# PIC.net
KiCad netlist of a schematic drawn in Altium Designer
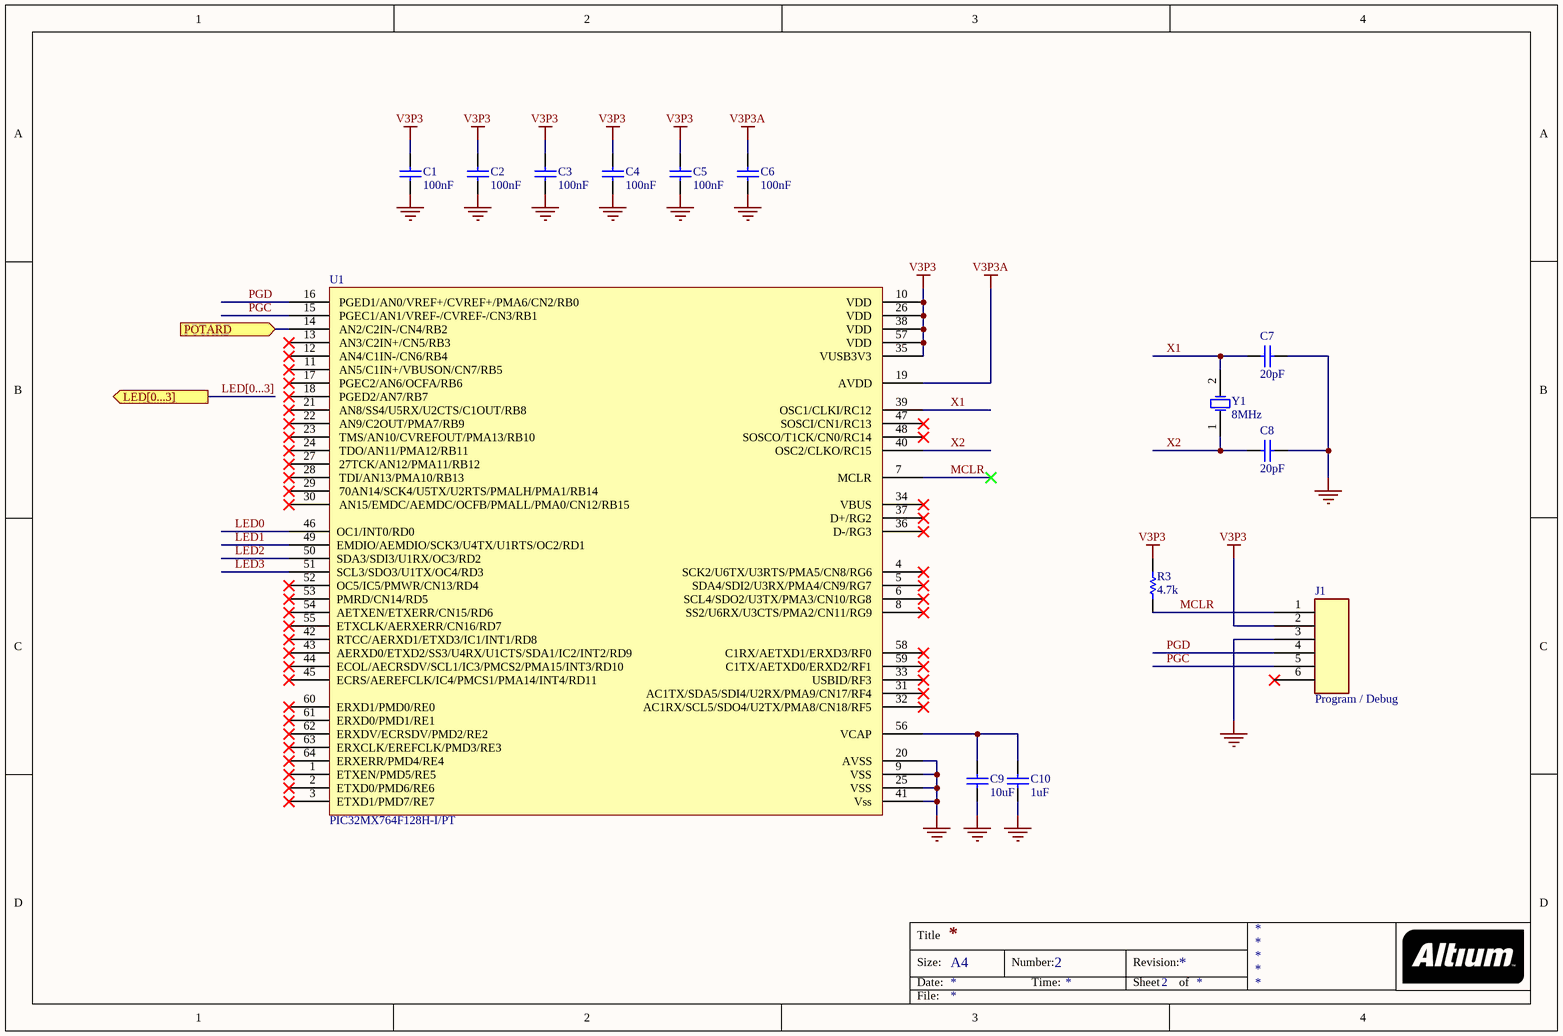
[diagram p0: PIC.SchDoc]

(export (version "E")
  (design (tool "Eeschema 10.0.6"))
  (components
    (comp (ref "C1")
      (value "100nF")
      (footprint "CAPC1608N")
      (description "Capacitor")
      (fields (field (name "PUBLISHER") "Altium Limited"))
      (libsource (lib "Miscellaneous Devices") (part "Cap"))
    )
    (comp (ref "C2")
      (value "100nF")
      (footprint "CAPC1608N")
      (description "Capacitor")
      (fields (field (name "PUBLISHER") "Altium Limited"))
      (libsource (lib "Miscellaneous Devices") (part "Cap"))
    )
    (comp (ref "C3")
      (value "100nF")
      (footprint "CAPC1608N")
      (description "Capacitor")
      (fields (field (name "PUBLISHER") "Altium Limited"))
      (libsource (lib "Miscellaneous Devices") (part "Cap"))
    )
    (comp (ref "C4")
      (value "100nF")
      (footprint "CAPC1608N")
      (description "Capacitor")
      (fields (field (name "PUBLISHER") "Altium Limited"))
      (libsource (lib "Miscellaneous Devices") (part "Cap"))
    )
    (comp (ref "C5")
      (value "100nF")
      (footprint "CAPC1608N")
      (description "Capacitor")
      (fields (field (name "PUBLISHER") "Altium Limited"))
      (libsource (lib "Miscellaneous Devices") (part "Cap"))
    )
    (comp (ref "C6")
      (value "100nF")
      (footprint "CAPC1608N")
      (description "Capacitor")
      (fields (field (name "PUBLISHER") "Altium Limited"))
      (libsource (lib "Miscellaneous Devices") (part "Cap"))
    )
    (comp (ref "C7")
      (value "20pF")
      (footprint "CAPC1005N")
      (description "Capacitor")
      (fields (field (name "PUBLISHER") "Altium Limited"))
      (libsource (lib "Miscellaneous Devices") (part "Cap"))
    )
    (comp (ref "C8")
      (value "20pF")
      (footprint "CAPC1005N")
      (description "Capacitor")
      (fields (field (name "PUBLISHER") "Altium Limited"))
      (libsource (lib "Miscellaneous Devices") (part "Cap"))
    )
    (comp (ref "C9")
      (value "10uF")
      (footprint "CAPC2012N")
      (description "Capacitor")
      (fields (field (name "PUBLISHER") "Altium Limited"))
      (libsource (lib "Miscellaneous Devices") (part "Cap"))
    )
    (comp (ref "C10")
      (value "1uF")
      (footprint "CAPC1608N")
      (description "Capacitor")
      (fields (field (name "PUBLISHER") "Altium Limited"))
      (libsource (lib "Miscellaneous Devices") (part "Cap"))
    )
    (comp (ref "J1")
      (value "Program / Debug")
      (fields (field (name "NAME") "J1") (field (name "TYPE") "Program / Debug"))
      (libsource (lib "TP02_SCHLib") (part "Program / Debug"))
    )
    (comp (ref "R3")
      (value "4.7k")
      (footprint "RESC1608N")
      (description "Resistor")
      (fields (field (name "PUBLISHER") "Altium Limited"))
      (libsource (lib "Miscellaneous Devices") (part "Res1"))
    )
    (comp (ref "U1")
      (value "PIC32MX764F128H-I/PT")
      (footprint "QFP50P1200X1200X120-64")
      (description "PIC32MX764F128H")
      (libsource (lib "TP02_SCHLib") (part "PIC"))
    )
    (comp (ref "Y1")
      (value "8MHz")
      (footprint "XTAL139X50X45")
      (description "Crystal Oscillator")
      (fields (field (name "PUBLISHER") "Altium Limited"))
      (libsource (lib "Miscellaneous Devices") (part "XTAL"))
    )
  )
  (nets
    (net (code "2") (name "/LED0") (class "Default")
      (node (ref "U1") (pin "46") (pinfunction "OC1/INT0/RD0_46") (pintype "passive"))
    )
    (net (code "3") (name "/LED1") (class "Default")
      (node (ref "U1") (pin "49") (pinfunction "EMDIO/AEMDIO/SCK3/U4TX/U1RTS/OC2/RD1_49") (pintype "passive"))
    )
    (net (code "4") (name "/LED2") (class "Default")
      (node (ref "U1") (pin "50") (pinfunction "SDA3/SDI3/U1RX/OC3/RD2_50") (pintype "passive"))
    )
    (net (code "5") (name "/LED3") (class "Default")
      (node (ref "U1") (pin "51") (pinfunction "SCL3/SDO3/U1TX/OC4/RD3_51") (pintype "passive"))
    )
    (net (code "6") (name "/MCLR") (class "Default")
      (node (ref "J1") (pin "1") (pintype "passive"))
      (node (ref "R3") (pin "1") (pinfunction "1_1") (pintype "passive"))
      (node (ref "U1") (pin "7") (pinfunction "MCLR_7") (pintype "passive"))
    )
    (net (code "7") (name "/PGC") (class "Default")
      (node (ref "J1") (pin "5") (pinfunction "68_5") (pintype "passive"))
      (node (ref "U1") (pin "15") (pinfunction "PGEC1/AN1/VREF-/CVREF-/CN3/RB1_15") (pintype "passive"))
    )
    (net (code "8") (name "/PGD") (class "Default")
      (node (ref "J1") (pin "4") (pinfunction "67_4") (pintype "passive"))
      (node (ref "U1") (pin "16") (pinfunction "PGED1/AN0/VREF+/CVREF+/PMA6/CN2/RB0_16") (pintype "passive"))
    )
    (net (code "9") (name "/POTARD") (class "Default")
      (node (ref "U1") (pin "14") (pinfunction "AN2/C2IN-/CN4/RB2_14") (pintype "passive"))
    )
    (net (code "10") (name "/X1") (class "Default")
      (node (ref "C7") (pin "2") (pinfunction "2_2") (pintype "passive"))
      (node (ref "U1") (pin "39") (pinfunction "OSC1/CLKI/RC12_39") (pintype "passive"))
      (node (ref "Y1") (pin "2") (pinfunction "OSC2_2") (pintype "passive"))
    )
    (net (code "11") (name "/X2") (class "Default")
      (node (ref "C8") (pin "1") (pinfunction "1_1") (pintype "passive"))
      (node (ref "U1") (pin "40") (pinfunction "OSC2/CLKO/RC15_40") (pintype "passive"))
      (node (ref "Y1") (pin "1") (pinfunction "OSC1_1") (pintype "passive"))
    )
    (net (code "13") (name "GND") (class "Default")
      (node (ref "C1") (pin "1") (pinfunction "1_1") (pintype "passive"))
      (node (ref "C10") (pin "2") (pinfunction "2_2") (pintype "passive"))
      (node (ref "C2") (pin "1") (pinfunction "1_1") (pintype "passive"))
      (node (ref "C3") (pin "1") (pinfunction "1_1") (pintype "passive"))
      (node (ref "C4") (pin "1") (pinfunction "1_1") (pintype "passive"))
      (node (ref "C5") (pin "1") (pinfunction "1_1") (pintype "passive"))
      (node (ref "C6") (pin "1") (pinfunction "1_1") (pintype "passive"))
      (node (ref "C7") (pin "1") (pinfunction "1_1") (pintype "passive"))
      (node (ref "C8") (pin "2") (pinfunction "2_2") (pintype "passive"))
      (node (ref "C9") (pin "1") (pinfunction "1_1") (pintype "passive"))
      (node (ref "J1") (pin "3") (pintype "passive"))
      (node (ref "U1") (pin "20") (pinfunction "AVSS_20") (pintype "passive"))
      (node (ref "U1") (pin "25") (pinfunction "VSS_25") (pintype "passive"))
      (node (ref "U1") (pin "41") (pinfunction "Vss_41") (pintype "passive"))
      (node (ref "U1") (pin "9") (pinfunction "VSS_9") (pintype "passive"))
    )
    (net (code "14") (name "Net-(U1-VCAP)") (class "Default")
      (node (ref "C10") (pin "1") (pinfunction "1_1") (pintype "passive"))
      (node (ref "C9") (pin "2") (pinfunction "2_2") (pintype "passive"))
      (node (ref "U1") (pin "56") (pinfunction "VCAP_56") (pintype "passive"))
    )
    (net (code "15") (name "V3P3") (class "Default")
      (node (ref "C1") (pin "2") (pinfunction "2_2") (pintype "passive"))
      (node (ref "C2") (pin "2") (pinfunction "2_2") (pintype "passive"))
      (node (ref "C3") (pin "2") (pinfunction "2_2") (pintype "passive"))
      (node (ref "C4") (pin "2") (pinfunction "2_2") (pintype "passive"))
      (node (ref "C5") (pin "2") (pinfunction "2_2") (pintype "passive"))
      (node (ref "J1") (pin "2") (pinfunction "65_2") (pintype "passive"))
      (node (ref "R3") (pin "2") (pinfunction "2_2") (pintype "passive"))
      (node (ref "U1") (pin "10") (pinfunction "VDD_10") (pintype "passive"))
      (node (ref "U1") (pin "26") (pinfunction "VDD_26") (pintype "passive"))
      (node (ref "U1") (pin "35") (pinfunction "VUSB3V3_35") (pintype "passive"))
      (node (ref "U1") (pin "38") (pinfunction "VDD_38") (pintype "passive"))
      (node (ref "U1") (pin "57") (pinfunction "VDD_57") (pintype "passive"))
    )
    (net (code "16") (name "V3P3A") (class "Default")
      (node (ref "C6") (pin "2") (pinfunction "2_2") (pintype "passive"))
      (node (ref "U1") (pin "19") (pinfunction "AVDD_19") (pintype "passive"))
    )
    (net (code "17") (name "unconnected-(J1-69-Pad6)") (class "Default")
      (node (ref "J1") (pin "6") (pinfunction "69_6") (pintype "power_in+no_connect"))
    )
    (net (code "18") (name "unconnected-(U1-27TCK{slash}AN12{slash}PMA11{slash}RB12-Pad27)") (class "Default")
      (node (ref "U1") (pin "27") (pinfunction "27TCK/AN12/PMA11/RB12_27") (pintype "passive+no_connect"))
    )
    (net (code "19") (name "unconnected-(U1-70AN14{slash}SCK4{slash}U5TX{slash}U2RTS{slash}PMALH{slash}PMA1{slash}RB14-Pad29)") (class "Default")
      (node (ref "U1") (pin "29") (pinfunction "70AN14/SCK4/U5TX/U2RTS/PMALH/PMA1/RB14_29") (pintype "passive+no_connect"))
    )
    (net (code "20") (name "unconnected-(U1-AC1RX{slash}SCL5{slash}SDO4{slash}U2TX{slash}PMA8{slash}CN18{slash}RF5-Pad32)") (class "Default")
      (node (ref "U1") (pin "32") (pinfunction "AC1RX/SCL5/SDO4/U2TX/PMA8/CN18/RF5_32") (pintype "passive+no_connect"))
    )
    (net (code "21") (name "unconnected-(U1-AC1TX{slash}SDA5{slash}SDI4{slash}U2RX{slash}PMA9{slash}CN17{slash}RF4-Pad31)") (class "Default")
      (node (ref "U1") (pin "31") (pinfunction "AC1TX/SDA5/SDI4/U2RX/PMA9/CN17/RF4_31") (pintype "passive+no_connect"))
    )
    (net (code "22") (name "unconnected-(U1-AERXD0{slash}ETXD2{slash}SS3{slash}U4RX{slash}U1CTS{slash}SDA1{slash}IC2{slash}INT2{slash}RD9-Pad43)") (class "Default")
      (node (ref "U1") (pin "43") (pinfunction "AERXD0/ETXD2/SS3/U4RX/U1CTS/SDA1/IC2/INT2/RD9_43") (pintype "passive+no_connect"))
    )
    (net (code "23") (name "unconnected-(U1-AETXEN{slash}ETXERR{slash}CN15{slash}RD6-Pad54)") (class "Default")
      (node (ref "U1") (pin "54") (pinfunction "AETXEN/ETXERR/CN15/RD6_54") (pintype "passive+no_connect"))
    )
    (net (code "24") (name "unconnected-(U1-AN3{slash}C2IN+{slash}CN5{slash}RB3-Pad13)") (class "Default")
      (node (ref "U1") (pin "13") (pinfunction "AN3/C2IN+/CN5/RB3_13") (pintype "passive+no_connect"))
    )
    (net (code "25") (name "unconnected-(U1-AN4{slash}C1IN-{slash}CN6{slash}RB4-Pad12)") (class "Default")
      (node (ref "U1") (pin "12") (pinfunction "AN4/C1IN-/CN6/RB4_12") (pintype "passive+no_connect"))
    )
    (net (code "26") (name "unconnected-(U1-AN5{slash}C1IN+{slash}VBUSON{slash}CN7{slash}RB5-Pad11)") (class "Default")
      (node (ref "U1") (pin "11") (pinfunction "AN5/C1IN+/VBUSON/CN7/RB5_11") (pintype "passive+no_connect"))
    )
    (net (code "27") (name "unconnected-(U1-AN8{slash}SS4{slash}U5RX{slash}U2CTS{slash}C1OUT{slash}RB8-Pad21)") (class "Default")
      (node (ref "U1") (pin "21") (pinfunction "AN8/SS4/U5RX/U2CTS/C1OUT/RB8_21") (pintype "passive+no_connect"))
    )
    (net (code "28") (name "unconnected-(U1-AN9{slash}C2OUT{slash}PMA7{slash}RB9-Pad22)") (class "Default")
      (node (ref "U1") (pin "22") (pinfunction "AN9/C2OUT/PMA7/RB9_22") (pintype "passive+no_connect"))
    )
    (net (code "29") (name "unconnected-(U1-AN15{slash}EMDC{slash}AEMDC{slash}OCFB{slash}PMALL{slash}PMA0{slash}CN12{slash}RB15-Pad30)") (class "Default")
      (node (ref "U1") (pin "30") (pinfunction "AN15/EMDC/AEMDC/OCFB/PMALL/PMA0/CN12/RB15_30") (pintype "passive+no_connect"))
    )
    (net (code "30") (name "unconnected-(U1-C1RX{slash}AETXD1{slash}ERXD3{slash}RF0-Pad58)") (class "Default")
      (node (ref "U1") (pin "58") (pinfunction "C1RX/AETXD1/ERXD3/RF0_58") (pintype "passive+no_connect"))
    )
    (net (code "31") (name "unconnected-(U1-C1TX{slash}AETXD0{slash}ERXD2{slash}RF1-Pad59)") (class "Default")
      (node (ref "U1") (pin "59") (pinfunction "C1TX/AETXD0/ERXD2/RF1_59") (pintype "passive+no_connect"))
    )
    (net (code "32") (name "unconnected-(U1-D+{slash}RG2-Pad37)") (class "Default")
      (node (ref "U1") (pin "37") (pinfunction "D+/RG2_37") (pintype "passive+no_connect"))
    )
    (net (code "33") (name "unconnected-(U1-D-{slash}RG3-Pad36)") (class "Default")
      (node (ref "U1") (pin "36") (pinfunction "D-/RG3_36") (pintype "passive+no_connect"))
    )
    (net (code "34") (name "unconnected-(U1-ECOL{slash}AECRSDV{slash}SCL1{slash}IC3{slash}PMCS2{slash}PMA15{slash}INT3{slash}RD10-Pad44)") (class "Default")
      (node (ref "U1") (pin "44") (pinfunction "ECOL/AECRSDV/SCL1/IC3/PMCS2/PMA15/INT3/RD10_44") (pintype "passive+no_connect"))
    )
    (net (code "35") (name "unconnected-(U1-ECRS{slash}AEREFCLK{slash}IC4{slash}PMCS1{slash}PMA14{slash}INT4{slash}RD11-Pad45)") (class "Default")
      (node (ref "U1") (pin "45") (pinfunction "ECRS/AEREFCLK/IC4/PMCS1/PMA14/INT4/RD11_45") (pintype "passive+no_connect"))
    )
    (net (code "36") (name "unconnected-(U1-ERXCLK{slash}EREFCLK{slash}PMD3{slash}RE3-Pad63)") (class "Default")
      (node (ref "U1") (pin "63") (pinfunction "ERXCLK/EREFCLK/PMD3/RE3_63") (pintype "passive+no_connect"))
    )
    (net (code "37") (name "unconnected-(U1-ERXD0{slash}PMD1{slash}RE1-Pad61)") (class "Default")
      (node (ref "U1") (pin "61") (pinfunction "ERXD0/PMD1/RE1_61") (pintype "passive+no_connect"))
    )
    (net (code "38") (name "unconnected-(U1-ERXD1{slash}PMD0{slash}RE0-Pad60)") (class "Default")
      (node (ref "U1") (pin "60") (pinfunction "ERXD1/PMD0/RE0_60") (pintype "passive+no_connect"))
    )
    (net (code "39") (name "unconnected-(U1-ERXDV{slash}ECRSDV{slash}PMD2{slash}RE2-Pad62)") (class "Default")
      (node (ref "U1") (pin "62") (pinfunction "ERXDV/ECRSDV/PMD2/RE2_62") (pintype "passive+no_connect"))
    )
    (net (code "40") (name "unconnected-(U1-ERXERR{slash}PMD4{slash}RE4-Pad64)") (class "Default")
      (node (ref "U1") (pin "64") (pinfunction "ERXERR/PMD4/RE4_64") (pintype "passive+no_connect"))
    )
    (net (code "41") (name "unconnected-(U1-ETXCLK{slash}AERXERR{slash}CN16{slash}RD7-Pad55)") (class "Default")
      (node (ref "U1") (pin "55") (pinfunction "ETXCLK/AERXERR/CN16/RD7_55") (pintype "passive+no_connect"))
    )
    (net (code "42") (name "unconnected-(U1-ETXD0{slash}PMD6{slash}RE6-Pad2)") (class "Default")
      (node (ref "U1") (pin "2") (pinfunction "ETXD0/PMD6/RE6_2") (pintype "passive+no_connect"))
    )
    (net (code "43") (name "unconnected-(U1-ETXD1{slash}PMD7{slash}RE7-Pad3)") (class "Default")
      (node (ref "U1") (pin "3") (pinfunction "ETXD1/PMD7/RE7_3") (pintype "passive+no_connect"))
    )
    (net (code "44") (name "unconnected-(U1-ETXEN{slash}PMD5{slash}RE5-Pad1)") (class "Default")
      (node (ref "U1") (pin "1") (pinfunction "ETXEN/PMD5/RE5_1") (pintype "passive+no_connect"))
    )
    (net (code "45") (name "unconnected-(U1-OC5{slash}IC5{slash}PMWR{slash}CN13{slash}RD4-Pad52)") (class "Default")
      (node (ref "U1") (pin "52") (pinfunction "OC5/IC5/PMWR/CN13/RD4_52") (pintype "passive+no_connect"))
    )
    (net (code "46") (name "unconnected-(U1-PGEC2{slash}AN6{slash}OCFA{slash}RB6-Pad17)") (class "Default")
      (node (ref "U1") (pin "17") (pinfunction "PGEC2/AN6/OCFA/RB6_17") (pintype "passive+no_connect"))
    )
    (net (code "47") (name "unconnected-(U1-PGED2{slash}AN7{slash}RB7-Pad18)") (class "Default")
      (node (ref "U1") (pin "18") (pinfunction "PGED2/AN7/RB7_18") (pintype "passive+no_connect"))
    )
    (net (code "48") (name "unconnected-(U1-PMRD{slash}CN14{slash}RD5-Pad53)") (class "Default")
      (node (ref "U1") (pin "53") (pinfunction "PMRD/CN14/RD5_53") (pintype "passive+no_connect"))
    )
    (net (code "49") (name "unconnected-(U1-RTCC{slash}AERXD1{slash}ETXD3{slash}IC1{slash}INT1{slash}RD8-Pad42)") (class "Default")
      (node (ref "U1") (pin "42") (pinfunction "RTCC/AERXD1/ETXD3/IC1/INT1/RD8_42") (pintype "passive+no_connect"))
    )
    (net (code "50") (name "unconnected-(U1-SCK2{slash}U6TX{slash}U3RTS{slash}PMA5{slash}CN8{slash}RG6-Pad4)") (class "Default")
      (node (ref "U1") (pin "4") (pinfunction "SCK2/U6TX/U3RTS/PMA5/CN8/RG6_4") (pintype "passive+no_connect"))
    )
    (net (code "51") (name "unconnected-(U1-SCL4{slash}SDO2{slash}U3TX{slash}PMA3{slash}CN10{slash}RG8-Pad6)") (class "Default")
      (node (ref "U1") (pin "6") (pinfunction "SCL4/SDO2/U3TX/PMA3/CN10/RG8_6") (pintype "passive+no_connect"))
    )
    (net (code "52") (name "unconnected-(U1-SDA4{slash}SDI2{slash}U3RX{slash}PMA4{slash}CN9{slash}RG7-Pad5)") (class "Default")
      (node (ref "U1") (pin "5") (pinfunction "SDA4/SDI2/U3RX/PMA4/CN9/RG7_5") (pintype "passive+no_connect"))
    )
    (net (code "53") (name "unconnected-(U1-SOSCI{slash}CN1{slash}RC13-Pad47)") (class "Default")
      (node (ref "U1") (pin "47") (pinfunction "SOSCI/CN1/RC13_47") (pintype "passive+no_connect"))
    )
    (net (code "54") (name "unconnected-(U1-SOSCO{slash}T1CK{slash}CN0{slash}RC14-Pad48)") (class "Default")
      (node (ref "U1") (pin "48") (pinfunction "SOSCO/T1CK/CN0/RC14_48") (pintype "passive+no_connect"))
    )
    (net (code "55") (name "unconnected-(U1-SS2{slash}U6RX{slash}U3CTS{slash}PMA2{slash}CN11{slash}RG9-Pad8)") (class "Default")
      (node (ref "U1") (pin "8") (pinfunction "SS2/U6RX/U3CTS/PMA2/CN11/RG9_8") (pintype "passive+no_connect"))
    )
    (net (code "56") (name "unconnected-(U1-TDI{slash}AN13{slash}PMA10{slash}RB13-Pad28)") (class "Default")
      (node (ref "U1") (pin "28") (pinfunction "TDI/AN13/PMA10/RB13_28") (pintype "passive+no_connect"))
    )
    (net (code "57") (name "unconnected-(U1-TDO{slash}AN11{slash}PMA12{slash}RB11-Pad24)") (class "Default")
      (node (ref "U1") (pin "24") (pinfunction "TDO/AN11/PMA12/RB11_24") (pintype "passive+no_connect"))
    )
    (net (code "58") (name "unconnected-(U1-TMS{slash}AN10{slash}CVREFOUT{slash}PMA13{slash}RB10-Pad23)") (class "Default")
      (node (ref "U1") (pin "23") (pinfunction "TMS/AN10/CVREFOUT/PMA13/RB10_23") (pintype "passive+no_connect"))
    )
    (net (code "59") (name "unconnected-(U1-USBID{slash}RF3-Pad33)") (class "Default")
      (node (ref "U1") (pin "33") (pinfunction "USBID/RF3_33") (pintype "passive+no_connect"))
    )
    (net (code "60") (name "unconnected-(U1-VBUS-Pad34)") (class "Default")
      (node (ref "U1") (pin "34") (pinfunction "VBUS_34") (pintype "passive+no_connect"))
    )
  )
)
